# FPGA.net
KiCad netlist of a schematic drawn in Altium Designer
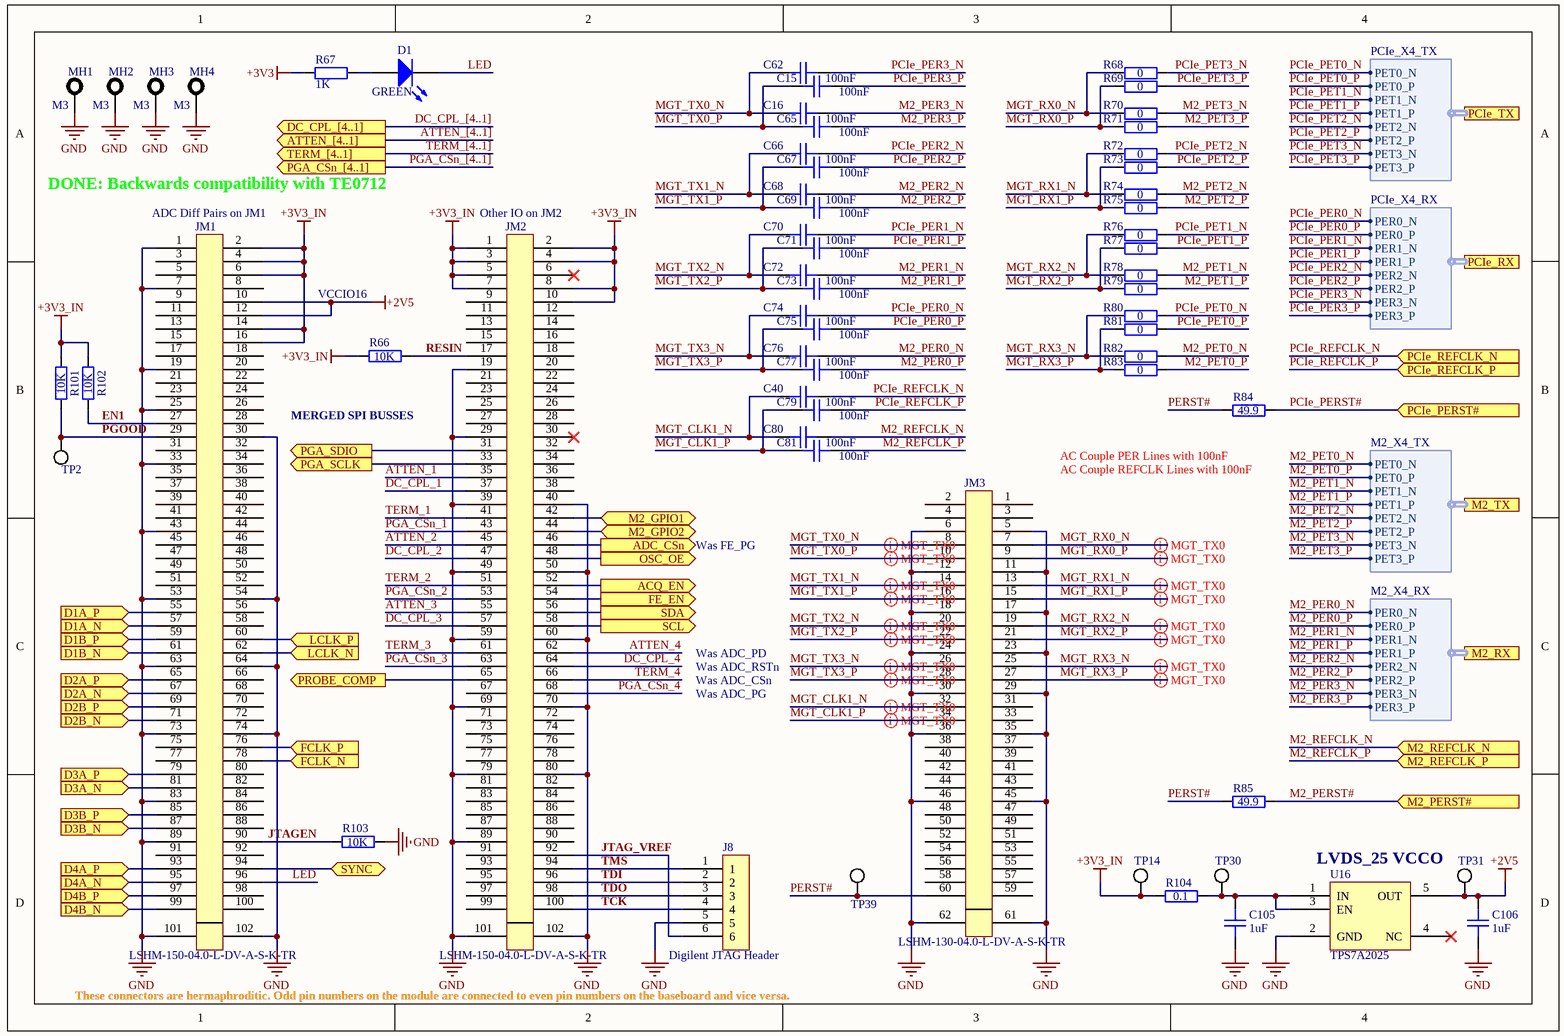
[diagram p0: FPGA.SchDoc]

(export (version "E")
  (design (tool "Eeschema 10.0.6"))
  (components
    (comp (ref "C15")
      (value "100nF")
      (footprint "GEN_C_0201")
      (libsource (lib "DSO") (part "CAP 100nF 6.3V X5R 0201"))
    )
    (comp (ref "C16")
      (value "100nF")
      (footprint "GEN_C_0201")
      (libsource (lib "DSO") (part "CAP 100nF 6.3V X5R 0201"))
    )
    (comp (ref "C40")
      (value "100nF")
      (footprint "GEN_C_0201")
      (libsource (lib "DSO") (part "CAP 100nF 6.3V X5R 0201"))
    )
    (comp (ref "C62")
      (value "100nF")
      (footprint "GEN_C_0201")
      (libsource (lib "DSO") (part "CAP 100nF 6.3V X5R 0201"))
    )
    (comp (ref "C65")
      (value "100nF")
      (footprint "GEN_C_0201")
      (libsource (lib "DSO") (part "CAP 100nF 6.3V X5R 0201"))
    )
    (comp (ref "C66")
      (value "100nF")
      (footprint "GEN_C_0201")
      (libsource (lib "DSO") (part "CAP 100nF 6.3V X5R 0201"))
    )
    (comp (ref "C67")
      (value "100nF")
      (footprint "GEN_C_0201")
      (libsource (lib "DSO") (part "CAP 100nF 6.3V X5R 0201"))
    )
    (comp (ref "C68")
      (value "100nF")
      (footprint "GEN_C_0201")
      (libsource (lib "DSO") (part "CAP 100nF 6.3V X5R 0201"))
    )
    (comp (ref "C69")
      (value "100nF")
      (footprint "GEN_C_0201")
      (libsource (lib "DSO") (part "CAP 100nF 6.3V X5R 0201"))
    )
    (comp (ref "C70")
      (value "100nF")
      (footprint "GEN_C_0201")
      (libsource (lib "DSO") (part "CAP 100nF 6.3V X5R 0201"))
    )
    (comp (ref "C71")
      (value "100nF")
      (footprint "GEN_C_0201")
      (libsource (lib "DSO") (part "CAP 100nF 6.3V X5R 0201"))
    )
    (comp (ref "C72")
      (value "100nF")
      (footprint "GEN_C_0201")
      (libsource (lib "DSO") (part "CAP 100nF 6.3V X5R 0201"))
    )
    (comp (ref "C73")
      (value "100nF")
      (footprint "GEN_C_0201")
      (libsource (lib "DSO") (part "CAP 100nF 6.3V X5R 0201"))
    )
    (comp (ref "C74")
      (value "100nF")
      (footprint "GEN_C_0201")
      (libsource (lib "DSO") (part "CAP 100nF 6.3V X5R 0201"))
    )
    (comp (ref "C75")
      (value "100nF")
      (footprint "GEN_C_0201")
      (libsource (lib "DSO") (part "CAP 100nF 6.3V X5R 0201"))
    )
    (comp (ref "C76")
      (value "100nF")
      (footprint "GEN_C_0201")
      (libsource (lib "DSO") (part "CAP 100nF 6.3V X5R 0201"))
    )
    (comp (ref "C77")
      (value "100nF")
      (footprint "GEN_C_0201")
      (libsource (lib "DSO") (part "CAP 100nF 6.3V X5R 0201"))
    )
    (comp (ref "C79")
      (value "100nF")
      (footprint "GEN_C_0201")
      (libsource (lib "DSO") (part "CAP 100nF 6.3V X5R 0201"))
    )
    (comp (ref "C80")
      (value "100nF")
      (footprint "GEN_C_0201")
      (libsource (lib "DSO") (part "CAP 100nF 6.3V X5R 0201"))
    )
    (comp (ref "C81")
      (value "100nF")
      (footprint "GEN_C_0201")
      (libsource (lib "DSO") (part "CAP 100nF 6.3V X5R 0201"))
    )
    (comp (ref "C105")
      (value "1uF")
      (footprint "GEN_C_0402")
      (libsource (lib "DSO") (part "CAP 1uF 25V X5R 0402"))
    )
    (comp (ref "C106")
      (value "1uF")
      (footprint "GEN_C_0402")
      (libsource (lib "DSO") (part "CAP 1uF 25V X5R 0402"))
    )
    (comp (ref "D1")
      (value "GREEN")
      (footprint "LED_0603_LTST-S270K")
      (libsource (lib "DSO") (part "LED GREEN 0603 LTST-S270K"))
    )
    (comp (ref "J8")
      (value "2.54mm 6 Pin TH")
      (footprint "GEN_2.54mm_6_Pin_TH_RA")
      (libsource (lib "DSO") (part "CONN 2.54mm 6 Pin TH RA"))
    )
    (comp (ref "JM1")
      (value "LSHM-150-04.0-L-DV-A-S-K-TR")
      (footprint "SAM_LSHM-150-XX.X-XX-DV-A-S")
      (libsource (lib "DSO") (part "CONN LSHM-150-04.0-L-DV-A-S-K-TR"))
    )
    (comp (ref "JM2")
      (value "LSHM-150-04.0-L-DV-A-S-K-TR")
      (footprint "SAM_LSHM-150-XX.X-XX-DV-A-S")
      (libsource (lib "DSO") (part "CONN LSHM-150-04.0-L-DV-A-S-K-TR"))
    )
    (comp (ref "JM3")
      (value "LSHM-130-04.0-L-DV-A-S-K-TR")
      (footprint "SAM_LSHM-130-XX.X-XX-DV-A-S")
      (libsource (lib "DSO") (part "CONN LSHM-130-04.0-L-DV-A-S-K-TR"))
    )
    (comp (ref "MH1") (value "M3") (footprint "MH M3") (libsource (lib "DSO") (part "MH M3")))
    (comp (ref "MH2") (value "M3") (footprint "MH M3") (libsource (lib "DSO") (part "MH M3")))
    (comp (ref "MH3") (value "M3") (footprint "MH M3") (libsource (lib "DSO") (part "MH M3")))
    (comp (ref "MH4") (value "M3") (footprint "MH M3") (libsource (lib "DSO") (part "MH M3")))
    (comp (ref "R66")
      (value "10K")
      (footprint "GEN_R_0402")
      (fields (field (name "TOLERANCE") "1%"))
      (libsource (lib "") (part "RES 10K OHM 1% 1/10W 0402_1"))
    )
    (comp (ref "R67")
      (value "1K")
      (footprint "GEN_R_0402")
      (fields (field (name "TOLERANCE") "1%"))
      (libsource (lib "DSO") (part "RES 1K OHM 1% 1/10W 0402"))
    )
    (comp (ref "R68")
      (value "0")
      (footprint "GEN_R_0201")
      (fields (field (name "TOLERANCE") "1%"))
      (libsource (lib "DSO") (part "RES 0 OHM 1% 1/20W 0201"))
    )
    (comp (ref "R69")
      (value "0")
      (footprint "GEN_R_0201")
      (fields (field (name "TOLERANCE") "1%"))
      (libsource (lib "DSO") (part "RES 0 OHM 1% 1/20W 0201"))
    )
    (comp (ref "R70")
      (value "0")
      (footprint "GEN_R_0201")
      (fields (field (name "TOLERANCE") "1%"))
      (libsource (lib "DSO") (part "RES 0 OHM 1% 1/20W 0201"))
    )
    (comp (ref "R71")
      (value "0")
      (footprint "GEN_R_0201")
      (fields (field (name "TOLERANCE") "1%"))
      (libsource (lib "DSO") (part "RES 0 OHM 1% 1/20W 0201"))
    )
    (comp (ref "R72")
      (value "0")
      (footprint "GEN_R_0201")
      (fields (field (name "TOLERANCE") "1%"))
      (libsource (lib "DSO") (part "RES 0 OHM 1% 1/20W 0201"))
    )
    (comp (ref "R73")
      (value "0")
      (footprint "GEN_R_0201")
      (fields (field (name "TOLERANCE") "1%"))
      (libsource (lib "DSO") (part "RES 0 OHM 1% 1/20W 0201"))
    )
    (comp (ref "R74")
      (value "0")
      (footprint "GEN_R_0201")
      (fields (field (name "TOLERANCE") "1%"))
      (libsource (lib "DSO") (part "RES 0 OHM 1% 1/20W 0201"))
    )
    (comp (ref "R75")
      (value "0")
      (footprint "GEN_R_0201")
      (fields (field (name "TOLERANCE") "1%"))
      (libsource (lib "DSO") (part "RES 0 OHM 1% 1/20W 0201"))
    )
    (comp (ref "R76")
      (value "0")
      (footprint "GEN_R_0201")
      (fields (field (name "TOLERANCE") "1%"))
      (libsource (lib "DSO") (part "RES 0 OHM 1% 1/20W 0201"))
    )
    (comp (ref "R77")
      (value "0")
      (footprint "GEN_R_0201")
      (fields (field (name "TOLERANCE") "1%"))
      (libsource (lib "DSO") (part "RES 0 OHM 1% 1/20W 0201"))
    )
    (comp (ref "R78")
      (value "0")
      (footprint "GEN_R_0201")
      (fields (field (name "TOLERANCE") "1%"))
      (libsource (lib "DSO") (part "RES 0 OHM 1% 1/20W 0201"))
    )
    (comp (ref "R79")
      (value "0")
      (footprint "GEN_R_0201")
      (fields (field (name "TOLERANCE") "1%"))
      (libsource (lib "DSO") (part "RES 0 OHM 1% 1/20W 0201"))
    )
    (comp (ref "R80")
      (value "0")
      (footprint "GEN_R_0201")
      (fields (field (name "TOLERANCE") "1%"))
      (libsource (lib "DSO") (part "RES 0 OHM 1% 1/20W 0201"))
    )
    (comp (ref "R81")
      (value "0")
      (footprint "GEN_R_0201")
      (fields (field (name "TOLERANCE") "1%"))
      (libsource (lib "DSO") (part "RES 0 OHM 1% 1/20W 0201"))
    )
    (comp (ref "R82")
      (value "0")
      (footprint "GEN_R_0201")
      (fields (field (name "TOLERANCE") "1%"))
      (libsource (lib "DSO") (part "RES 0 OHM 1% 1/20W 0201"))
    )
    (comp (ref "R83")
      (value "0")
      (footprint "GEN_R_0201")
      (fields (field (name "TOLERANCE") "1%"))
      (libsource (lib "DSO") (part "RES 0 OHM 1% 1/20W 0201"))
    )
    (comp (ref "R84")
      (value "49.9")
      (footprint "GEN_R_0402")
      (fields (field (name "TOLERANCE") "1%"))
      (libsource (lib "DSO") (part "RES 49.9 OHM 1% 1/10W 0402"))
    )
    (comp (ref "R85")
      (value "49.9")
      (footprint "GEN_R_0402")
      (fields (field (name "TOLERANCE") "1%"))
      (libsource (lib "DSO") (part "RES 49.9 OHM 1% 1/10W 0402"))
    )
    (comp (ref "R101")
      (value "10K")
      (footprint "GEN_R_0402")
      (fields (field (name "TOLERANCE") "1%"))
      (libsource (lib "DSO") (part "RES 10K OHM 1% 1/10W 0402"))
    )
    (comp (ref "R102")
      (value "10K")
      (footprint "GEN_R_0402")
      (fields (field (name "TOLERANCE") "1%"))
      (libsource (lib "DSO") (part "RES 10K OHM 1% 1/10W 0402"))
    )
    (comp (ref "R103")
      (value "10K")
      (footprint "GEN_R_0402")
      (fields (field (name "TOLERANCE") "1%"))
      (libsource (lib "") (part "RES 10K OHM 1% 1/10W 0402_1"))
    )
    (comp (ref "R104")
      (value "0.1")
      (footprint "GEN_R_0402")
      (fields (field (name "TOLERANCE") "1%"))
      (libsource (lib "DSO") (part "RES 0.1 OHM 1% 1/6W 0402"))
    )
    (comp (ref "TP2") (value "PCB") (footprint "GEN_TP_PCB") (libsource (lib "DSO") (part "TP PCB 1mm")))
    (comp (ref "TP14") (value "PCB") (footprint "GEN_TP_PCB") (libsource (lib "DSO") (part "TP PCB 1mm")))
    (comp (ref "TP30") (value "PCB") (footprint "GEN_TP_PCB") (libsource (lib "DSO") (part "TP PCB 1mm")))
    (comp (ref "TP31") (value "PCB") (footprint "GEN_TP_PCB") (libsource (lib "DSO") (part "TP PCB 1mm")))
    (comp (ref "TP39") (value "PCB") (footprint "GEN_TP_PCB") (libsource (lib "DSO") (part "TP PCB 1mm")))
    (comp (ref "U16")
      (value "TPS7A2025")
      (footprint "GEN_SOT23_5_950_2900X1600X1450")
      (libsource (lib "DSO") (part "IC LDO TPS7A2025"))
    )
  )
  (nets
    (net (code "5") (name "+2V5") (class "Default")
      (node (ref "C106") (pin "2") (pinfunction "2_2") (pintype "passive"))
      (node (ref "JM1") (pin "10") (pinfunction "10_10") (pintype "passive"))
      (node (ref "JM1") (pin "12") (pinfunction "12_12") (pintype "passive"))
      (node (ref "TP31") (pin "1") (pinfunction "1_1") (pintype "passive"))
      (node (ref "U16") (pin "5") (pinfunction "OUT_5") (pintype "power_in"))
    )
    (net (code "6") (name "+3V3") (class "Default")
      (node (ref "R67") (pin "2") (pinfunction "2_2") (pintype "passive"))
    )
    (net (code "7") (name "+3V3_IN") (class "Default")
      (node (ref "JM1") (pin "14") (pinfunction "14_14") (pintype "passive"))
      (node (ref "JM1") (pin "16") (pinfunction "16_16") (pintype "passive"))
      (node (ref "JM1") (pin "2") (pinfunction "2_2") (pintype "passive"))
      (node (ref "JM1") (pin "4") (pinfunction "4_4") (pintype "passive"))
      (node (ref "JM1") (pin "6") (pinfunction "6_6") (pintype "passive"))
      (node (ref "JM2") (pin "1") (pinfunction "1_1") (pintype "passive"))
      (node (ref "JM2") (pin "10") (pinfunction "10_10") (pintype "passive"))
      (node (ref "JM2") (pin "2") (pinfunction "2_2") (pintype "passive"))
      (node (ref "JM2") (pin "3") (pinfunction "3_3") (pintype "passive"))
      (node (ref "JM2") (pin "4") (pinfunction "4_4") (pintype "passive"))
      (node (ref "JM2") (pin "5") (pinfunction "5_5") (pintype "passive"))
      (node (ref "JM2") (pin "7") (pinfunction "7_7") (pintype "passive"))
      (node (ref "JM2") (pin "8") (pinfunction "8_8") (pintype "passive"))
      (node (ref "R101") (pin "2") (pinfunction "2_2") (pintype "passive"))
      (node (ref "R102") (pin "2") (pinfunction "2_2") (pintype "passive"))
      (node (ref "R104") (pin "1") (pinfunction "1_1") (pintype "passive"))
      (node (ref "R66") (pin "2") (pinfunction "2_2") (pintype "passive"))
      (node (ref "TP14") (pin "1") (pinfunction "1_1") (pintype "passive"))
    )
    (net (code "8") (name "/ACQ_EN") (class "Default")
      (node (ref "JM2") (pin "52") (pinfunction "52_52") (pintype "passive"))
    )
    (net (code "9") (name "/ADC_CSn") (class "Default")
      (node (ref "JM2") (pin "46") (pinfunction "46_46") (pintype "passive"))
    )
    (net (code "10") (name "/ATTEN_1") (class "Default")
      (node (ref "JM2") (pin "35") (pinfunction "35_35") (pintype "passive"))
    )
    (net (code "11") (name "/ATTEN_2") (class "Default")
      (node (ref "JM2") (pin "45") (pinfunction "45_45") (pintype "passive"))
    )
    (net (code "12") (name "/ATTEN_3") (class "Default")
      (node (ref "JM2") (pin "55") (pinfunction "55_55") (pintype "passive"))
    )
    (net (code "13") (name "/ATTEN_4") (class "Default")
      (node (ref "JM2") (pin "62") (pinfunction "62_62") (pintype "passive"))
    )
    (net (code "15") (name "/D1A_N") (class "Default")
      (node (ref "JM1") (pin "57") (pinfunction "57_57") (pintype "passive"))
    )
    (net (code "16") (name "/D1A_P") (class "Default")
      (node (ref "JM1") (pin "55") (pinfunction "55_55") (pintype "passive"))
    )
    (net (code "17") (name "/D1B_N") (class "Default")
      (node (ref "JM1") (pin "61") (pinfunction "61_61") (pintype "passive"))
    )
    (net (code "18") (name "/D1B_P") (class "Default")
      (node (ref "JM1") (pin "59") (pinfunction "59_59") (pintype "passive"))
    )
    (net (code "19") (name "/D2A_N") (class "Default")
      (node (ref "JM1") (pin "67") (pinfunction "67_67") (pintype "passive"))
    )
    (net (code "20") (name "/D2A_P") (class "Default")
      (node (ref "JM1") (pin "65") (pinfunction "65_65") (pintype "passive"))
    )
    (net (code "21") (name "/D2B_N") (class "Default")
      (node (ref "JM1") (pin "71") (pinfunction "71_71") (pintype "passive"))
    )
    (net (code "22") (name "/D2B_P") (class "Default")
      (node (ref "JM1") (pin "69") (pinfunction "69_69") (pintype "passive"))
    )
    (net (code "23") (name "/D3A_N") (class "Default")
      (node (ref "JM1") (pin "81") (pinfunction "81_81") (pintype "passive"))
    )
    (net (code "24") (name "/D3A_P") (class "Default")
      (node (ref "JM1") (pin "79") (pinfunction "79_79") (pintype "passive"))
    )
    (net (code "25") (name "/D3B_N") (class "Default")
      (node (ref "JM1") (pin "87") (pinfunction "87_87") (pintype "passive"))
    )
    (net (code "26") (name "/D3B_P") (class "Default")
      (node (ref "JM1") (pin "85") (pinfunction "85_85") (pintype "passive"))
    )
    (net (code "27") (name "/D4A_N") (class "Default")
      (node (ref "JM1") (pin "95") (pinfunction "95_95") (pintype "passive"))
    )
    (net (code "28") (name "/D4A_P") (class "Default")
      (node (ref "JM1") (pin "93") (pinfunction "93_93") (pintype "passive"))
    )
    (net (code "29") (name "/D4B_N") (class "Default")
      (node (ref "JM1") (pin "99") (pinfunction "99_99") (pintype "passive"))
    )
    (net (code "30") (name "/D4B_P") (class "Default")
      (node (ref "JM1") (pin "97") (pinfunction "97_97") (pintype "passive"))
    )
    (net (code "31") (name "/DC_CPL_1") (class "Default")
      (node (ref "JM2") (pin "37") (pinfunction "37_37") (pintype "passive"))
    )
    (net (code "32") (name "/DC_CPL_2") (class "Default")
      (node (ref "JM2") (pin "47") (pinfunction "47_47") (pintype "passive"))
    )
    (net (code "33") (name "/DC_CPL_3") (class "Default")
      (node (ref "JM2") (pin "57") (pinfunction "57_57") (pintype "passive"))
    )
    (net (code "34") (name "/DC_CPL_4") (class "Default")
      (node (ref "JM2") (pin "64") (pinfunction "64_64") (pintype "passive"))
    )
    (net (code "36") (name "/EN1") (class "Default")
      (node (ref "JM1") (pin "27") (pinfunction "27_27") (pintype "passive"))
      (node (ref "R102") (pin "1") (pinfunction "1_1") (pintype "passive"))
    )
    (net (code "37") (name "/FCLK_N") (class "Default")
      (node (ref "JM1") (pin "78") (pinfunction "78_78") (pintype "passive"))
    )
    (net (code "38") (name "/FCLK_P") (class "Default")
      (node (ref "JM1") (pin "76") (pinfunction "76_76") (pintype "passive"))
    )
    (net (code "39") (name "/FE_EN") (class "Default")
      (node (ref "JM2") (pin "54") (pinfunction "54_54") (pintype "passive"))
    )
    (net (code "40") (name "/JTAGEN") (class "Default")
      (node (ref "JM1") (pin "90") (pinfunction "90_90") (pintype "passive"))
      (node (ref "R103") (pin "2") (pinfunction "2_2") (pintype "passive"))
    )
    (net (code "41") (name "/JTAG_VREF") (class "Default")
      (node (ref "J8") (pin "6") (pinfunction "6_6") (pintype "passive"))
      (node (ref "JM2") (pin "92") (pinfunction "92_92") (pintype "passive"))
    )
    (net (code "42") (name "/LCLK_N") (class "Default")
      (node (ref "JM1") (pin "62") (pinfunction "62_62") (pintype "passive"))
    )
    (net (code "43") (name "/LCLK_P") (class "Default")
      (node (ref "JM1") (pin "60") (pinfunction "60_60") (pintype "passive"))
    )
    (net (code "44") (name "/LED") (class "Default")
      (node (ref "D1") (pin "1") (pinfunction "K_1") (pintype "passive"))
      (node (ref "JM1") (pin "96") (pinfunction "96_96") (pintype "passive"))
    )
    (net (code "45") (name "/M2_GPIO1") (class "Default")
      (node (ref "JM2") (pin "42") (pinfunction "42_42") (pintype "passive"))
    )
    (net (code "46") (name "/M2_GPIO2") (class "Default")
      (node (ref "JM2") (pin "44") (pinfunction "44_44") (pintype "passive"))
    )
    (net (code "47") (name "/M2_PER0_N") (class "Default")
      (node (ref "C76") (pin "1") (pinfunction "1_1") (pintype "passive"))
    )
    (net (code "48") (name "/M2_PER0_P") (class "Default")
      (node (ref "C77") (pin "1") (pinfunction "1_1") (pintype "passive"))
    )
    (net (code "49") (name "/M2_PER1_N") (class "Default")
      (node (ref "C72") (pin "1") (pinfunction "1_1") (pintype "passive"))
    )
    (net (code "50") (name "/M2_PER1_P") (class "Default")
      (node (ref "C73") (pin "1") (pinfunction "1_1") (pintype "passive"))
    )
    (net (code "51") (name "/M2_PER2_N") (class "Default")
      (node (ref "C68") (pin "1") (pinfunction "1_1") (pintype "passive"))
    )
    (net (code "52") (name "/M2_PER2_P") (class "Default")
      (node (ref "C69") (pin "1") (pinfunction "1_1") (pintype "passive"))
    )
    (net (code "53") (name "/M2_PER3_N") (class "Default")
      (node (ref "C16") (pin "1") (pinfunction "1_1") (pintype "passive"))
    )
    (net (code "54") (name "/M2_PER3_P") (class "Default")
      (node (ref "C65") (pin "1") (pinfunction "1_1") (pintype "passive"))
    )
    (net (code "55") (name "/M2_PERST#") (class "Default")
      (node (ref "R85") (pin "2") (pinfunction "2_2") (pintype "passive"))
    )
    (net (code "56") (name "/M2_PET0_N") (class "Default")
      (node (ref "R82") (pin "2") (pinfunction "2_2") (pintype "passive"))
    )
    (net (code "57") (name "/M2_PET0_P") (class "Default")
      (node (ref "R83") (pin "2") (pinfunction "2_2") (pintype "passive"))
    )
    (net (code "58") (name "/M2_PET1_N") (class "Default")
      (node (ref "R78") (pin "2") (pinfunction "2_2") (pintype "passive"))
    )
    (net (code "59") (name "/M2_PET1_P") (class "Default")
      (node (ref "R79") (pin "2") (pinfunction "2_2") (pintype "passive"))
    )
    (net (code "60") (name "/M2_PET2_N") (class "Default")
      (node (ref "R74") (pin "2") (pinfunction "2_2") (pintype "passive"))
    )
    (net (code "61") (name "/M2_PET2_P") (class "Default")
      (node (ref "R75") (pin "2") (pinfunction "2_2") (pintype "passive"))
    )
    (net (code "62") (name "/M2_PET3_N") (class "Default")
      (node (ref "R70") (pin "2") (pinfunction "2_2") (pintype "passive"))
    )
    (net (code "63") (name "/M2_PET3_P") (class "Default")
      (node (ref "R71") (pin "2") (pinfunction "2_2") (pintype "passive"))
    )
    (net (code "64") (name "/M2_REFCLK_N") (class "Default")
      (node (ref "C80") (pin "1") (pinfunction "1_1") (pintype "passive"))
    )
    (net (code "65") (name "/M2_REFCLK_P") (class "Default")
      (node (ref "C81") (pin "1") (pinfunction "1_1") (pintype "passive"))
    )
    (net (code "66") (name "/MGT_CLK1_N") (class "Default")
      (node (ref "C40") (pin "2") (pinfunction "2_2") (pintype "passive"))
      (node (ref "C80") (pin "2") (pinfunction "2_2") (pintype "passive"))
      (node (ref "JM3") (pin "32") (pinfunction "32_32") (pintype "passive"))
    )
    (net (code "67") (name "/MGT_CLK1_P") (class "Default")
      (node (ref "C79") (pin "2") (pinfunction "2_2") (pintype "passive"))
      (node (ref "C81") (pin "2") (pinfunction "2_2") (pintype "passive"))
      (node (ref "JM3") (pin "34") (pinfunction "34_34") (pintype "passive"))
    )
    (net (code "68") (name "/MGT_RX0_N") (class "Default")
      (node (ref "JM3") (pin "7") (pinfunction "7_7") (pintype "passive"))
      (node (ref "R68") (pin "1") (pinfunction "1_1") (pintype "passive"))
      (node (ref "R70") (pin "1") (pinfunction "1_1") (pintype "passive"))
    )
    (net (code "69") (name "/MGT_RX0_P") (class "Default")
      (node (ref "JM3") (pin "9") (pinfunction "9_9") (pintype "passive"))
      (node (ref "R69") (pin "1") (pinfunction "1_1") (pintype "passive"))
      (node (ref "R71") (pin "1") (pinfunction "1_1") (pintype "passive"))
    )
    (net (code "70") (name "/MGT_RX1_N") (class "Default")
      (node (ref "JM3") (pin "13") (pinfunction "13_13") (pintype "passive"))
      (node (ref "R72") (pin "1") (pinfunction "1_1") (pintype "passive"))
      (node (ref "R74") (pin "1") (pinfunction "1_1") (pintype "passive"))
    )
    (net (code "71") (name "/MGT_RX1_P") (class "Default")
      (node (ref "JM3") (pin "15") (pinfunction "15_15") (pintype "passive"))
      (node (ref "R73") (pin "1") (pinfunction "1_1") (pintype "passive"))
      (node (ref "R75") (pin "1") (pinfunction "1_1") (pintype "passive"))
    )
    (net (code "72") (name "/MGT_RX2_N") (class "Default")
      (node (ref "JM3") (pin "19") (pinfunction "19_19") (pintype "passive"))
      (node (ref "R76") (pin "1") (pinfunction "1_1") (pintype "passive"))
      (node (ref "R78") (pin "1") (pinfunction "1_1") (pintype "passive"))
    )
    (net (code "73") (name "/MGT_RX2_P") (class "Default")
      (node (ref "JM3") (pin "21") (pinfunction "21_21") (pintype "passive"))
      (node (ref "R77") (pin "1") (pinfunction "1_1") (pintype "passive"))
      (node (ref "R79") (pin "1") (pinfunction "1_1") (pintype "passive"))
    )
    (net (code "74") (name "/MGT_RX3_N") (class "Default")
      (node (ref "JM3") (pin "25") (pinfunction "25_25") (pintype "passive"))
      (node (ref "R80") (pin "1") (pinfunction "1_1") (pintype "passive"))
      (node (ref "R82") (pin "1") (pinfunction "1_1") (pintype "passive"))
    )
    (net (code "75") (name "/MGT_RX3_P") (class "Default")
      (node (ref "JM3") (pin "27") (pinfunction "27_27") (pintype "passive"))
      (node (ref "R81") (pin "1") (pinfunction "1_1") (pintype "passive"))
      (node (ref "R83") (pin "1") (pinfunction "1_1") (pintype "passive"))
    )
    (net (code "76") (name "/MGT_TX0_N") (class "Default")
      (node (ref "C16") (pin "2") (pinfunction "2_2") (pintype "passive"))
      (node (ref "C62") (pin "2") (pinfunction "2_2") (pintype "passive"))
      (node (ref "JM3") (pin "8") (pinfunction "8_8") (pintype "passive"))
    )
    (net (code "77") (name "/MGT_TX0_P") (class "Default")
      (node (ref "C15") (pin "2") (pinfunction "2_2") (pintype "passive"))
      (node (ref "C65") (pin "2") (pinfunction "2_2") (pintype "passive"))
      (node (ref "JM3") (pin "10") (pinfunction "10_10") (pintype "passive"))
    )
    (net (code "78") (name "/MGT_TX1_N") (class "Default")
      (node (ref "C66") (pin "2") (pinfunction "2_2") (pintype "passive"))
      (node (ref "C68") (pin "2") (pinfunction "2_2") (pintype "passive"))
      (node (ref "JM3") (pin "14") (pinfunction "14_14") (pintype "passive"))
    )
    (net (code "79") (name "/MGT_TX1_P") (class "Default")
      (node (ref "C67") (pin "2") (pinfunction "2_2") (pintype "passive"))
      (node (ref "C69") (pin "2") (pinfunction "2_2") (pintype "passive"))
      (node (ref "JM3") (pin "16") (pinfunction "16_16") (pintype "passive"))
    )
    (net (code "80") (name "/MGT_TX2_N") (class "Default")
      (node (ref "C70") (pin "2") (pinfunction "2_2") (pintype "passive"))
      (node (ref "C72") (pin "2") (pinfunction "2_2") (pintype "passive"))
      (node (ref "JM3") (pin "20") (pinfunction "20_20") (pintype "passive"))
    )
    (net (code "81") (name "/MGT_TX2_P") (class "Default")
      (node (ref "C71") (pin "2") (pinfunction "2_2") (pintype "passive"))
      (node (ref "C73") (pin "2") (pinfunction "2_2") (pintype "passive"))
      (node (ref "JM3") (pin "22") (pinfunction "22_22") (pintype "passive"))
    )
    (net (code "82") (name "/MGT_TX3_N") (class "Default")
      (node (ref "C74") (pin "2") (pinfunction "2_2") (pintype "passive"))
      (node (ref "C76") (pin "2") (pinfunction "2_2") (pintype "passive"))
      (node (ref "JM3") (pin "26") (pinfunction "26_26") (pintype "passive"))
    )
    (net (code "83") (name "/MGT_TX3_P") (class "Default")
      (node (ref "C75") (pin "2") (pinfunction "2_2") (pintype "passive"))
      (node (ref "C77") (pin "2") (pinfunction "2_2") (pintype "passive"))
      (node (ref "JM3") (pin "28") (pinfunction "28_28") (pintype "passive"))
    )
    (net (code "84") (name "/OSC_OE") (class "Default")
      (node (ref "JM2") (pin "48") (pinfunction "48_48") (pintype "passive"))
    )
    (net (code "85") (name "/PCIe_PER0_N") (class "Default")
      (node (ref "C74") (pin "1") (pinfunction "1_1") (pintype "passive"))
    )
    (net (code "86") (name "/PCIe_PER0_P") (class "Default")
      (node (ref "C75") (pin "1") (pinfunction "1_1") (pintype "passive"))
    )
    (net (code "87") (name "/PCIe_PER1_N") (class "Default")
      (node (ref "C70") (pin "1") (pinfunction "1_1") (pintype "passive"))
    )
    (net (code "88") (name "/PCIe_PER1_P") (class "Default")
      (node (ref "C71") (pin "1") (pinfunction "1_1") (pintype "passive"))
    )
    (net (code "89") (name "/PCIe_PER2_N") (class "Default")
      (node (ref "C66") (pin "1") (pinfunction "1_1") (pintype "passive"))
    )
    (net (code "90") (name "/PCIe_PER2_P") (class "Default")
      (node (ref "C67") (pin "1") (pinfunction "1_1") (pintype "passive"))
    )
    (net (code "91") (name "/PCIe_PER3_N") (class "Default")
      (node (ref "C62") (pin "1") (pinfunction "1_1") (pintype "passive"))
    )
    (net (code "92") (name "/PCIe_PER3_P") (class "Default")
      (node (ref "C15") (pin "1") (pinfunction "1_1") (pintype "passive"))
    )
    (net (code "93") (name "/PCIe_PERST#") (class "Default")
      (node (ref "R84") (pin "2") (pinfunction "2_2") (pintype "passive"))
    )
    (net (code "94") (name "/PCIe_PET0_N") (class "Default")
      (node (ref "R80") (pin "2") (pinfunction "2_2") (pintype "passive"))
    )
    (net (code "95") (name "/PCIe_PET0_P") (class "Default")
      (node (ref "R81") (pin "2") (pinfunction "2_2") (pintype "passive"))
    )
    (net (code "96") (name "/PCIe_PET1_N") (class "Default")
      (node (ref "R76") (pin "2") (pinfunction "2_2") (pintype "passive"))
    )
    (net (code "97") (name "/PCIe_PET1_P") (class "Default")
      (node (ref "R77") (pin "2") (pinfunction "2_2") (pintype "passive"))
    )
    (net (code "98") (name "/PCIe_PET2_N") (class "Default")
      (node (ref "R72") (pin "2") (pinfunction "2_2") (pintype "passive"))
    )
    (net (code "99") (name "/PCIe_PET2_P") (class "Default")
      (node (ref "R73") (pin "2") (pinfunction "2_2") (pintype "passive"))
    )
    (net (code "100") (name "/PCIe_PET3_N") (class "Default")
      (node (ref "R68") (pin "2") (pinfunction "2_2") (pintype "passive"))
    )
    (net (code "101") (name "/PCIe_PET3_P") (class "Default")
      (node (ref "R69") (pin "2") (pinfunction "2_2") (pintype "passive"))
    )
    (net (code "102") (name "/PCIe_REFCLK_N") (class "Default")
      (node (ref "C40") (pin "1") (pinfunction "1_1") (pintype "passive"))
    )
    (net (code "103") (name "/PCIe_REFCLK_P") (class "Default")
      (node (ref "C79") (pin "1") (pinfunction "1_1") (pintype "passive"))
    )
    (net (code "104") (name "/PERST#") (class "Default")
      (node (ref "JM3") (pin "60") (pinfunction "60_60") (pintype "passive"))
      (node (ref "R84") (pin "1") (pinfunction "1_1") (pintype "passive"))
      (node (ref "R85") (pin "1") (pinfunction "1_1") (pintype "passive"))
      (node (ref "TP39") (pin "1") (pinfunction "1_1") (pintype "passive"))
    )
    (net (code "105") (name "/PGA_CSn_1") (class "Default")
      (node (ref "JM2") (pin "43") (pinfunction "43_43") (pintype "passive"))
    )
    (net (code "106") (name "/PGA_CSn_2") (class "Default")
      (node (ref "JM2") (pin "53") (pinfunction "53_53") (pintype "passive"))
    )
    (net (code "107") (name "/PGA_CSn_3") (class "Default")
      (node (ref "JM2") (pin "63") (pinfunction "63_63") (pintype "passive"))
    )
    (net (code "108") (name "/PGA_CSn_4") (class "Default")
      (node (ref "JM2") (pin "68") (pinfunction "68_68") (pintype "passive"))
    )
    (net (code "110") (name "/PGA_SCLK") (class "Default")
      (node (ref "JM2") (pin "33") (pinfunction "33_33") (pintype "passive"))
    )
    (net (code "111") (name "/PGA_SDIO") (class "Default")
      (node (ref "JM2") (pin "31") (pinfunction "31_31") (pintype "passive"))
    )
    (net (code "112") (name "/PGOOD") (class "Default")
      (node (ref "JM1") (pin "29") (pinfunction "29_29") (pintype "passive"))
      (node (ref "R101") (pin "1") (pinfunction "1_1") (pintype "passive"))
      (node (ref "TP2") (pin "1") (pinfunction "1_1") (pintype "passive"))
    )
    (net (code "113") (name "/PROBE_COMP") (class "Default")
      (node (ref "JM2") (pin "65") (pinfunction "65_65") (pintype "passive"))
    )
    (net (code "114") (name "/RESIN") (class "Default")
      (node (ref "JM2") (pin "17") (pinfunction "17_17") (pintype "passive"))
      (node (ref "R66") (pin "1") (pinfunction "1_1") (pintype "passive"))
    )
    (net (code "115") (name "/SCL") (class "Default")
      (node (ref "JM2") (pin "58") (pinfunction "58_58") (pintype "passive"))
    )
    (net (code "116") (name "/SDA") (class "Default")
      (node (ref "JM2") (pin "56") (pinfunction "56_56") (pintype "passive"))
    )
    (net (code "117") (name "/SYNC") (class "Default")
      (node (ref "JM1") (pin "94") (pinfunction "94_94") (pintype "passive"))
    )
    (net (code "118") (name "/TCK") (class "Default")
      (node (ref "J8") (pin "4") (pinfunction "4_4") (pintype "passive"))
      (node (ref "JM2") (pin "100") (pinfunction "100_100") (pintype "passive"))
    )
    (net (code "119") (name "/TDI") (class "Default")
      (node (ref "J8") (pin "2") (pinfunction "2_2") (pintype "passive"))
      (node (ref "JM2") (pin "96") (pinfunction "96_96") (pintype "passive"))
    )
    (net (code "120") (name "/TDO") (class "Default")
      (node (ref "J8") (pin "3") (pinfunction "3_3") (pintype "passive"))
      (node (ref "JM2") (pin "98") (pinfunction "98_98") (pintype "passive"))
    )
    (net (code "121") (name "/TERM_1") (class "Default")
      (node (ref "JM2") (pin "41") (pinfunction "41_41") (pintype "passive"))
    )
    (net (code "122") (name "/TERM_2") (class "Default")
      (node (ref "JM2") (pin "51") (pinfunction "51_51") (pintype "passive"))
    )
    (net (code "123") (name "/TERM_3") (class "Default")
      (node (ref "JM2") (pin "61") (pinfunction "61_61") (pintype "passive"))
    )
    (net (code "124") (name "/TERM_4") (class "Default")
      (node (ref "JM2") (pin "66") (pinfunction "66_66") (pintype "passive"))
    )
    (net (code "126") (name "/TMS") (class "Default")
      (node (ref "J8") (pin "1") (pinfunction "1_1") (pintype "passive"))
      (node (ref "JM2") (pin "94") (pinfunction "94_94") (pintype "passive"))
    )
    (net (code "131") (name "GND") (class "Default")
      (node (ref "C105") (pin "1") (pinfunction "1_1") (pintype "passive"))
      (node (ref "C106") (pin "1") (pinfunction "1_1") (pintype "passive"))
      (node (ref "J8") (pin "5") (pinfunction "5_5") (pintype "passive"))
      (node (ref "JM1") (pin "1") (pinfunction "1_1") (pintype "passive"))
      (node (ref "JM1") (pin "101") (pinfunction "101_101") (pintype "passive"))
      (node (ref "JM1") (pin "102") (pinfunction "102_102") (pintype "passive"))
      (node (ref "JM1") (pin "19") (pinfunction "19_19") (pintype "passive"))
      (node (ref "JM1") (pin "25") (pinfunction "25_25") (pintype "passive"))
      (node (ref "JM1") (pin "30") (pinfunction "30_30") (pintype "passive"))
      (node (ref "JM1") (pin "33") (pinfunction "33_33") (pintype "passive"))
      (node (ref "JM1") (pin "43") (pinfunction "43_43") (pintype "passive"))
      (node (ref "JM1") (pin "53") (pinfunction "53_53") (pintype "passive"))
      (node (ref "JM1") (pin "54") (pinfunction "54_54") (pintype "passive"))
      (node (ref "JM1") (pin "63") (pinfunction "63_63") (pintype "passive"))
      (node (ref "JM1") (pin "64") (pinfunction "64_64") (pintype "passive"))
      (node (ref "JM1") (pin "7") (pinfunction "7_7") (pintype "passive"))
      (node (ref "JM1") (pin "73") (pinfunction "73_73") (pintype "passive"))
      (node (ref "JM1") (pin "74") (pinfunction "74_74") (pintype "passive"))
      (node (ref "JM1") (pin "83") (pinfunction "83_83") (pintype "passive"))
      (node (ref "JM1") (pin "89") (pinfunction "89_89") (pintype "passive"))
      (node (ref "JM2") (pin "101") (pinfunction "101_101") (pintype "passive"))
      (node (ref "JM2") (pin "102") (pinfunction "102_102") (pintype "passive"))
      (node (ref "JM2") (pin "19") (pinfunction "19_19") (pintype "passive"))
      (node (ref "JM2") (pin "29") (pinfunction "29_29") (pintype "passive"))
      (node (ref "JM2") (pin "39") (pinfunction "39_39") (pintype "passive"))
      (node (ref "JM2") (pin "40") (pinfunction "40_40") (pintype "passive"))
      (node (ref "JM2") (pin "49") (pinfunction "49_49") (pintype "passive"))
      (node (ref "JM2") (pin "50") (pinfunction "50_50") (pintype "passive"))
      (node (ref "JM2") (pin "59") (pinfunction "59_59") (pintype "passive"))
      (node (ref "JM2") (pin "60") (pinfunction "60_60") (pintype "passive"))
      (node (ref "JM2") (pin "69") (pinfunction "69_69") (pintype "passive"))
      (node (ref "JM2") (pin "70") (pinfunction "70_70") (pintype "passive"))
      (node (ref "JM2") (pin "79") (pinfunction "79_79") (pintype "passive"))
      (node (ref "JM2") (pin "80") (pinfunction "80_80") (pintype "passive"))
      (node (ref "JM2") (pin "89") (pinfunction "89_89") (pintype "passive"))
      (node (ref "JM3") (pin "11") (pinfunction "11_11") (pintype "passive"))
      (node (ref "JM3") (pin "12") (pinfunction "12_12") (pintype "passive"))
      (node (ref "JM3") (pin "17") (pinfunction "17_17") (pintype "passive"))
      (node (ref "JM3") (pin "18") (pinfunction "18_18") (pintype "passive"))
      (node (ref "JM3") (pin "23") (pinfunction "23_23") (pintype "passive"))
      (node (ref "JM3") (pin "24") (pinfunction "24_24") (pintype "passive"))
      (node (ref "JM3") (pin "29") (pinfunction "29_29") (pintype "passive"))
      (node (ref "JM3") (pin "30") (pinfunction "30_30") (pintype "passive"))
      (node (ref "JM3") (pin "35") (pinfunction "35_35") (pintype "passive"))
      (node (ref "JM3") (pin "36") (pinfunction "36_36") (pintype "passive"))
      (node (ref "JM3") (pin "45") (pinfunction "45_45") (pintype "passive"))
      (node (ref "JM3") (pin "46") (pinfunction "46_46") (pintype "passive"))
      (node (ref "JM3") (pin "5") (pinfunction "5_5") (pintype "passive"))
      (node (ref "JM3") (pin "6") (pinfunction "6_6") (pintype "passive"))
      (node (ref "JM3") (pin "61") (pinfunction "61_61") (pintype "passive"))
      (node (ref "JM3") (pin "62") (pinfunction "62_62") (pintype "passive"))
      (node (ref "MH1") (pin "1") (pinfunction "1_1") (pintype "passive"))
      (node (ref "MH2") (pin "1") (pinfunction "1_1") (pintype "passive"))
      (node (ref "MH3") (pin "1") (pinfunction "1_1") (pintype "passive"))
      (node (ref "MH4") (pin "1") (pinfunction "1_1") (pintype "passive"))
      (node (ref "R103") (pin "1") (pinfunction "1_1") (pintype "passive"))
      (node (ref "U16") (pin "2") (pinfunction "GND_2") (pintype "power_in"))
    )
    (net (code "132") (name "Net-(D1-A)") (class "Default")
      (node (ref "D1") (pin "2") (pinfunction "A_2") (pintype "passive"))
      (node (ref "R67") (pin "1") (pinfunction "1_1") (pintype "passive"))
    )
    (net (code "133") (name "Net-(U16-EN)") (class "Default")
      (node (ref "C105") (pin "2") (pinfunction "2_2") (pintype "passive"))
      (node (ref "R104") (pin "2") (pinfunction "2_2") (pintype "passive"))
      (node (ref "TP30") (pin "1") (pinfunction "1_1") (pintype "passive"))
      (node (ref "U16") (pin "1") (pinfunction "IN_1") (pintype "power_in"))
      (node (ref "U16") (pin "3") (pinfunction "EN_3") (pintype "passive"))
    )
    (net (code "134") (name "unconnected-(JM1-Pad3)") (class "Default")
      (node (ref "JM1") (pin "3") (pinfunction "3_3") (pintype "passive"))
    )
    (net (code "135") (name "unconnected-(JM1-Pad5)") (class "Default")
      (node (ref "JM1") (pin "5") (pinfunction "5_5") (pintype "passive"))
    )
    (net (code "136") (name "unconnected-(JM1-Pad8)") (class "Default")
      (node (ref "JM1") (pin "8") (pinfunction "8_8") (pintype "passive"))
    )
    (net (code "137") (name "unconnected-(JM1-Pad9)") (class "Default")
      (node (ref "JM1") (pin "9") (pinfunction "9_9") (pintype "passive"))
    )
    (net (code "138") (name "unconnected-(JM1-Pad11)") (class "Default")
      (node (ref "JM1") (pin "11") (pinfunction "11_11") (pintype "passive"))
    )
    (net (code "139") (name "unconnected-(JM1-Pad13)") (class "Default")
      (node (ref "JM1") (pin "13") (pinfunction "13_13") (pintype "passive"))
    )
    (net (code "140") (name "unconnected-(JM1-Pad15)") (class "Default")
      (node (ref "JM1") (pin "15") (pinfunction "15_15") (pintype "passive"))
    )
    (net (code "141") (name "unconnected-(JM1-Pad17)") (class "Default")
      (node (ref "JM1") (pin "17") (pinfunction "17_17") (pintype "passive"))
    )
    (net (code "142") (name "unconnected-(JM1-Pad18)") (class "Default")
      (node (ref "JM1") (pin "18") (pinfunction "18_18") (pintype "passive"))
    )
    (net (code "143") (name "unconnected-(JM1-Pad20)") (class "Default")
      (node (ref "JM1") (pin "20") (pinfunction "20_20") (pintype "passive"))
    )
    (net (code "144") (name "unconnected-(JM1-Pad21)") (class "Default")
      (node (ref "JM1") (pin "21") (pinfunction "21_21") (pintype "passive"))
    )
    (net (code "145") (name "unconnected-(JM1-Pad22)") (class "Default")
      (node (ref "JM1") (pin "22") (pinfunction "22_22") (pintype "passive"))
    )
    (net (code "146") (name "unconnected-(JM1-Pad23)") (class "Default")
      (node (ref "JM1") (pin "23") (pinfunction "23_23") (pintype "passive"))
    )
    (net (code "147") (name "unconnected-(JM1-Pad24)") (class "Default")
      (node (ref "JM1") (pin "24") (pinfunction "24_24") (pintype "passive"))
    )
    (net (code "148") (name "unconnected-(JM1-Pad26)") (class "Default")
      (node (ref "JM1") (pin "26") (pinfunction "26_26") (pintype "passive"))
    )
    (net (code "149") (name "unconnected-(JM1-Pad28)") (class "Default")
      (node (ref "JM1") (pin "28") (pinfunction "28_28") (pintype "passive"))
    )
    (net (code "150") (name "unconnected-(JM1-Pad31)") (class "Default")
      (node (ref "JM1") (pin "31") (pinfunction "31_31") (pintype "passive"))
    )
    (net (code "151") (name "unconnected-(JM1-Pad32)") (class "Default")
      (node (ref "JM1") (pin "32") (pinfunction "32_32") (pintype "passive"))
    )
    (net (code "152") (name "unconnected-(JM1-Pad34)") (class "Default")
      (node (ref "JM1") (pin "34") (pinfunction "34_34") (pintype "passive"))
    )
    (net (code "153") (name "unconnected-(JM1-Pad35)") (class "Default")
      (node (ref "JM1") (pin "35") (pinfunction "35_35") (pintype "passive"))
    )
    (net (code "154") (name "unconnected-(JM1-Pad36)") (class "Default")
      (node (ref "JM1") (pin "36") (pinfunction "36_36") (pintype "passive"))
    )
    (net (code "155") (name "unconnected-(JM1-Pad37)") (class "Default")
      (node (ref "JM1") (pin "37") (pinfunction "37_37") (pintype "passive"))
    )
    (net (code "156") (name "unconnected-(JM1-Pad38)") (class "Default")
      (node (ref "JM1") (pin "38") (pinfunction "38_38") (pintype "passive"))
    )
    (net (code "157") (name "unconnected-(JM1-Pad39)") (class "Default")
      (node (ref "JM1") (pin "39") (pinfunction "39_39") (pintype "passive"))
    )
    (net (code "158") (name "unconnected-(JM1-Pad40)") (class "Default")
      (node (ref "JM1") (pin "40") (pinfunction "40_40") (pintype "passive"))
    )
    (net (code "159") (name "unconnected-(JM1-Pad41)") (class "Default")
      (node (ref "JM1") (pin "41") (pinfunction "41_41") (pintype "passive"))
    )
    (net (code "160") (name "unconnected-(JM1-Pad42)") (class "Default")
      (node (ref "JM1") (pin "42") (pinfunction "42_42") (pintype "passive"))
    )
    (net (code "161") (name "unconnected-(JM1-Pad44)") (class "Default")
      (node (ref "JM1") (pin "44") (pinfunction "44_44") (pintype "passive"))
    )
    (net (code "162") (name "unconnected-(JM1-Pad45)") (class "Default")
      (node (ref "JM1") (pin "45") (pinfunction "45_45") (pintype "passive"))
    )
    (net (code "163") (name "unconnected-(JM1-Pad46)") (class "Default")
      (node (ref "JM1") (pin "46") (pinfunction "46_46") (pintype "passive"))
    )
    (net (code "164") (name "unconnected-(JM1-Pad47)") (class "Default")
      (node (ref "JM1") (pin "47") (pinfunction "47_47") (pintype "passive"))
    )
    (net (code "165") (name "unconnected-(JM1-Pad48)") (class "Default")
      (node (ref "JM1") (pin "48") (pinfunction "48_48") (pintype "passive"))
    )
    (net (code "166") (name "unconnected-(JM1-Pad49)") (class "Default")
      (node (ref "JM1") (pin "49") (pinfunction "49_49") (pintype "passive"))
    )
    (net (code "167") (name "unconnected-(JM1-Pad50)") (class "Default")
      (node (ref "JM1") (pin "50") (pinfunction "50_50") (pintype "passive"))
    )
    (net (code "168") (name "unconnected-(JM1-Pad51)") (class "Default")
      (node (ref "JM1") (pin "51") (pinfunction "51_51") (pintype "passive"))
    )
    (net (code "169") (name "unconnected-(JM1-Pad52)") (class "Default")
      (node (ref "JM1") (pin "52") (pinfunction "52_52") (pintype "passive"))
    )
    (net (code "170") (name "unconnected-(JM1-Pad56)") (class "Default")
      (node (ref "JM1") (pin "56") (pinfunction "56_56") (pintype "passive"))
    )
    (net (code "171") (name "unconnected-(JM1-Pad58)") (class "Default")
      (node (ref "JM1") (pin "58") (pinfunction "58_58") (pintype "passive"))
    )
    (net (code "172") (name "unconnected-(JM1-Pad66)") (class "Default")
      (node (ref "JM1") (pin "66") (pinfunction "66_66") (pintype "passive"))
    )
    (net (code "173") (name "unconnected-(JM1-Pad68)") (class "Default")
      (node (ref "JM1") (pin "68") (pinfunction "68_68") (pintype "passive"))
    )
    (net (code "174") (name "unconnected-(JM1-Pad70)") (class "Default")
      (node (ref "JM1") (pin "70") (pinfunction "70_70") (pintype "passive"))
    )
    (net (code "175") (name "unconnected-(JM1-Pad72)") (class "Default")
      (node (ref "JM1") (pin "72") (pinfunction "72_72") (pintype "passive"))
    )
    (net (code "176") (name "unconnected-(JM1-Pad75)") (class "Default")
      (node (ref "JM1") (pin "75") (pinfunction "75_75") (pintype "passive"))
    )
    (net (code "177") (name "unconnected-(JM1-Pad77)") (class "Default")
      (node (ref "JM1") (pin "77") (pinfunction "77_77") (pintype "passive"))
    )
    (net (code "178") (name "unconnected-(JM1-Pad80)") (class "Default")
      (node (ref "JM1") (pin "80") (pinfunction "80_80") (pintype "passive"))
    )
    (net (code "179") (name "unconnected-(JM1-Pad82)") (class "Default")
      (node (ref "JM1") (pin "82") (pinfunction "82_82") (pintype "passive"))
    )
    (net (code "180") (name "unconnected-(JM1-Pad84)") (class "Default")
      (node (ref "JM1") (pin "84") (pinfunction "84_84") (pintype "passive"))
    )
    (net (code "181") (name "unconnected-(JM1-Pad86)") (class "Default")
      (node (ref "JM1") (pin "86") (pinfunction "86_86") (pintype "passive"))
    )
    (net (code "182") (name "unconnected-(JM1-Pad88)") (class "Default")
      (node (ref "JM1") (pin "88") (pinfunction "88_88") (pintype "passive"))
    )
    (net (code "183") (name "unconnected-(JM1-Pad91)") (class "Default")
      (node (ref "JM1") (pin "91") (pinfunction "91_91") (pintype "passive"))
    )
    (net (code "184") (name "unconnected-(JM1-Pad92)") (class "Default")
      (node (ref "JM1") (pin "92") (pinfunction "92_92") (pintype "passive"))
    )
    (net (code "185") (name "unconnected-(JM1-Pad98)") (class "Default")
      (node (ref "JM1") (pin "98") (pinfunction "98_98") (pintype "passive"))
    )
    (net (code "186") (name "unconnected-(JM1-Pad100)") (class "Default")
      (node (ref "JM1") (pin "100") (pinfunction "100_100") (pintype "passive"))
    )
    (net (code "187") (name "unconnected-(JM2-Pad6)") (class "Default")
      (node (ref "JM2") (pin "6") (pinfunction "6_6") (pintype "passive+no_connect"))
    )
    (net (code "188") (name "unconnected-(JM2-Pad9)") (class "Default")
      (node (ref "JM2") (pin "9") (pinfunction "9_9") (pintype "passive"))
    )
    (net (code "189") (name "unconnected-(JM2-Pad11)") (class "Default")
      (node (ref "JM2") (pin "11") (pinfunction "11_11") (pintype "passive"))
    )
    (net (code "190") (name "unconnected-(JM2-Pad12)") (class "Default")
      (node (ref "JM2") (pin "12") (pinfunction "12_12") (pintype "passive"))
    )
    (net (code "191") (name "unconnected-(JM2-Pad13)") (class "Default")
      (node (ref "JM2") (pin "13") (pinfunction "13_13") (pintype "passive"))
    )
    (net (code "192") (name "unconnected-(JM2-Pad14)") (class "Default")
      (node (ref "JM2") (pin "14") (pinfunction "14_14") (pintype "passive"))
    )
    (net (code "193") (name "unconnected-(JM2-Pad15)") (class "Default")
      (node (ref "JM2") (pin "15") (pinfunction "15_15") (pintype "passive"))
    )
    (net (code "194") (name "unconnected-(JM2-Pad16)") (class "Default")
      (node (ref "JM2") (pin "16") (pinfunction "16_16") (pintype "passive"))
    )
    (net (code "195") (name "unconnected-(JM2-Pad18)") (class "Default")
      (node (ref "JM2") (pin "18") (pinfunction "18_18") (pintype "passive"))
    )
    (net (code "196") (name "unconnected-(JM2-Pad20)") (class "Default")
      (node (ref "JM2") (pin "20") (pinfunction "20_20") (pintype "passive"))
    )
    (net (code "197") (name "unconnected-(JM2-Pad21)") (class "Default")
      (node (ref "JM2") (pin "21") (pinfunction "21_21") (pintype "passive"))
    )
    (net (code "198") (name "unconnected-(JM2-Pad22)") (class "Default")
      (node (ref "JM2") (pin "22") (pinfunction "22_22") (pintype "passive"))
    )
    (net (code "199") (name "unconnected-(JM2-Pad23)") (class "Default")
      (node (ref "JM2") (pin "23") (pinfunction "23_23") (pintype "passive"))
    )
    (net (code "200") (name "unconnected-(JM2-Pad24)") (class "Default")
      (node (ref "JM2") (pin "24") (pinfunction "24_24") (pintype "passive"))
    )
    (net (code "201") (name "unconnected-(JM2-Pad25)") (class "Default")
      (node (ref "JM2") (pin "25") (pinfunction "25_25") (pintype "passive"))
    )
    (net (code "202") (name "unconnected-(JM2-Pad26)") (class "Default")
      (node (ref "JM2") (pin "26") (pinfunction "26_26") (pintype "passive"))
    )
    (net (code "203") (name "unconnected-(JM2-Pad27)") (class "Default")
      (node (ref "JM2") (pin "27") (pinfunction "27_27") (pintype "passive"))
    )
    (net (code "204") (name "unconnected-(JM2-Pad28)") (class "Default")
      (node (ref "JM2") (pin "28") (pinfunction "28_28") (pintype "passive"))
    )
    (net (code "205") (name "unconnected-(JM2-Pad30)") (class "Default")
      (node (ref "JM2") (pin "30") (pinfunction "30_30") (pintype "passive+no_connect"))
    )
    (net (code "206") (name "unconnected-(JM2-Pad32)") (class "Default")
      (node (ref "JM2") (pin "32") (pinfunction "32_32") (pintype "passive"))
    )
    (net (code "207") (name "unconnected-(JM2-Pad34)") (class "Default")
      (node (ref "JM2") (pin "34") (pinfunction "34_34") (pintype "passive"))
    )
    (net (code "208") (name "unconnected-(JM2-Pad36)") (class "Default")
      (node (ref "JM2") (pin "36") (pinfunction "36_36") (pintype "passive"))
    )
    (net (code "209") (name "unconnected-(JM2-Pad38)") (class "Default")
      (node (ref "JM2") (pin "38") (pinfunction "38_38") (pintype "passive"))
    )
    (net (code "210") (name "unconnected-(JM2-Pad67)") (class "Default")
      (node (ref "JM2") (pin "67") (pinfunction "67_67") (pintype "passive"))
    )
    (net (code "211") (name "unconnected-(JM2-Pad71)") (class "Default")
      (node (ref "JM2") (pin "71") (pinfunction "71_71") (pintype "passive"))
    )
    (net (code "212") (name "unconnected-(JM2-Pad72)") (class "Default")
      (node (ref "JM2") (pin "72") (pinfunction "72_72") (pintype "passive"))
    )
    (net (code "213") (name "unconnected-(JM2-Pad73)") (class "Default")
      (node (ref "JM2") (pin "73") (pinfunction "73_73") (pintype "passive"))
    )
    (net (code "214") (name "unconnected-(JM2-Pad74)") (class "Default")
      (node (ref "JM2") (pin "74") (pinfunction "74_74") (pintype "passive"))
    )
    (net (code "215") (name "unconnected-(JM2-Pad75)") (class "Default")
      (node (ref "JM2") (pin "75") (pinfunction "75_75") (pintype "passive"))
    )
    (net (code "216") (name "unconnected-(JM2-Pad76)") (class "Default")
      (node (ref "JM2") (pin "76") (pinfunction "76_76") (pintype "passive"))
    )
    (net (code "217") (name "unconnected-(JM2-Pad77)") (class "Default")
      (node (ref "JM2") (pin "77") (pinfunction "77_77") (pintype "passive"))
    )
    (net (code "218") (name "unconnected-(JM2-Pad78)") (class "Default")
      (node (ref "JM2") (pin "78") (pinfunction "78_78") (pintype "passive"))
    )
    (net (code "219") (name "unconnected-(JM2-Pad81)") (class "Default")
      (node (ref "JM2") (pin "81") (pinfunction "81_81") (pintype "passive"))
    )
    (net (code "220") (name "unconnected-(JM2-Pad82)") (class "Default")
      (node (ref "JM2") (pin "82") (pinfunction "82_82") (pintype "passive"))
    )
    (net (code "221") (name "unconnected-(JM2-Pad83)") (class "Default")
      (node (ref "JM2") (pin "83") (pinfunction "83_83") (pintype "passive"))
    )
    (net (code "222") (name "unconnected-(JM2-Pad84)") (class "Default")
      (node (ref "JM2") (pin "84") (pinfunction "84_84") (pintype "passive"))
    )
    (net (code "223") (name "unconnected-(JM2-Pad85)") (class "Default")
      (node (ref "JM2") (pin "85") (pinfunction "85_85") (pintype "passive"))
    )
    (net (code "224") (name "unconnected-(JM2-Pad86)") (class "Default")
      (node (ref "JM2") (pin "86") (pinfunction "86_86") (pintype "passive"))
    )
    (net (code "225") (name "unconnected-(JM2-Pad87)") (class "Default")
      (node (ref "JM2") (pin "87") (pinfunction "87_87") (pintype "passive"))
    )
    (net (code "226") (name "unconnected-(JM2-Pad88)") (class "Default")
      (node (ref "JM2") (pin "88") (pinfunction "88_88") (pintype "passive"))
    )
    (net (code "227") (name "unconnected-(JM2-Pad90)") (class "Default")
      (node (ref "JM2") (pin "90") (pinfunction "90_90") (pintype "passive"))
    )
    (net (code "228") (name "unconnected-(JM2-Pad91)") (class "Default")
      (node (ref "JM2") (pin "91") (pinfunction "91_91") (pintype "passive"))
    )
    (net (code "229") (name "unconnected-(JM2-Pad93)") (class "Default")
      (node (ref "JM2") (pin "93") (pinfunction "93_93") (pintype "passive"))
    )
    (net (code "230") (name "unconnected-(JM2-Pad95)") (class "Default")
      (node (ref "JM2") (pin "95") (pinfunction "95_95") (pintype "passive"))
    )
    (net (code "231") (name "unconnected-(JM2-Pad97)") (class "Default")
      (node (ref "JM2") (pin "97") (pinfunction "97_97") (pintype "passive"))
    )
    (net (code "232") (name "unconnected-(JM2-Pad99)") (class "Default")
      (node (ref "JM2") (pin "99") (pinfunction "99_99") (pintype "passive"))
    )
    (net (code "233") (name "unconnected-(JM3-Pad1)") (class "Default")
      (node (ref "JM3") (pin "1") (pinfunction "1_1") (pintype "passive"))
    )
    (net (code "234") (name "unconnected-(JM3-Pad2)") (class "Default")
      (node (ref "JM3") (pin "2") (pinfunction "2_2") (pintype "passive"))
    )
    (net (code "235") (name "unconnected-(JM3-Pad3)") (class "Default")
      (node (ref "JM3") (pin "3") (pinfunction "3_3") (pintype "passive"))
    )
    (net (code "236") (name "unconnected-(JM3-Pad4)") (class "Default")
      (node (ref "JM3") (pin "4") (pinfunction "4_4") (pintype "passive"))
    )
    (net (code "237") (name "unconnected-(JM3-Pad31)") (class "Default")
      (node (ref "JM3") (pin "31") (pinfunction "31_31") (pintype "passive"))
    )
    (net (code "238") (name "unconnected-(JM3-Pad33)") (class "Default")
      (node (ref "JM3") (pin "33") (pinfunction "33_33") (pintype "passive"))
    )
    (net (code "239") (name "unconnected-(JM3-Pad37)") (class "Default")
      (node (ref "JM3") (pin "37") (pinfunction "37_37") (pintype "passive"))
    )
    (net (code "240") (name "unconnected-(JM3-Pad38)") (class "Default")
      (node (ref "JM3") (pin "38") (pinfunction "38_38") (pintype "passive"))
    )
    (net (code "241") (name "unconnected-(JM3-Pad39)") (class "Default")
      (node (ref "JM3") (pin "39") (pinfunction "39_39") (pintype "passive"))
    )
    (net (code "242") (name "unconnected-(JM3-Pad40)") (class "Default")
      (node (ref "JM3") (pin "40") (pinfunction "40_40") (pintype "passive"))
    )
    (net (code "243") (name "unconnected-(JM3-Pad41)") (class "Default")
      (node (ref "JM3") (pin "41") (pinfunction "41_41") (pintype "passive"))
    )
    (net (code "244") (name "unconnected-(JM3-Pad42)") (class "Default")
      (node (ref "JM3") (pin "42") (pinfunction "42_42") (pintype "passive"))
    )
    (net (code "245") (name "unconnected-(JM3-Pad43)") (class "Default")
      (node (ref "JM3") (pin "43") (pinfunction "43_43") (pintype "passive"))
    )
    (net (code "246") (name "unconnected-(JM3-Pad44)") (class "Default")
      (node (ref "JM3") (pin "44") (pinfunction "44_44") (pintype "passive"))
    )
    (net (code "247") (name "unconnected-(JM3-Pad47)") (class "Default")
      (node (ref "JM3") (pin "47") (pinfunction "47_47") (pintype "passive"))
    )
    (net (code "248") (name "unconnected-(JM3-Pad48)") (class "Default")
      (node (ref "JM3") (pin "48") (pinfunction "48_48") (pintype "passive"))
    )
    (net (code "249") (name "unconnected-(JM3-Pad49)") (class "Default")
      (node (ref "JM3") (pin "49") (pinfunction "49_49") (pintype "passive"))
    )
    (net (code "250") (name "unconnected-(JM3-Pad50)") (class "Default")
      (node (ref "JM3") (pin "50") (pinfunction "50_50") (pintype "passive"))
    )
    (net (code "251") (name "unconnected-(JM3-Pad51)") (class "Default")
      (node (ref "JM3") (pin "51") (pinfunction "51_51") (pintype "passive"))
    )
    (net (code "252") (name "unconnected-(JM3-Pad52)") (class "Default")
      (node (ref "JM3") (pin "52") (pinfunction "52_52") (pintype "passive"))
    )
    (net (code "253") (name "unconnected-(JM3-Pad53)") (class "Default")
      (node (ref "JM3") (pin "53") (pinfunction "53_53") (pintype "passive"))
    )
    (net (code "254") (name "unconnected-(JM3-Pad54)") (class "Default")
      (node (ref "JM3") (pin "54") (pinfunction "54_54") (pintype "passive"))
    )
    (net (code "255") (name "unconnected-(JM3-Pad55)") (class "Default")
      (node (ref "JM3") (pin "55") (pinfunction "55_55") (pintype "passive"))
    )
    (net (code "256") (name "unconnected-(JM3-Pad56)") (class "Default")
      (node (ref "JM3") (pin "56") (pinfunction "56_56") (pintype "passive"))
    )
    (net (code "257") (name "unconnected-(JM3-Pad57)") (class "Default")
      (node (ref "JM3") (pin "57") (pinfunction "57_57") (pintype "passive"))
    )
    (net (code "258") (name "unconnected-(JM3-Pad58)") (class "Default")
      (node (ref "JM3") (pin "58") (pinfunction "58_58") (pintype "passive"))
    )
    (net (code "259") (name "unconnected-(JM3-Pad59)") (class "Default")
      (node (ref "JM3") (pin "59") (pinfunction "59_59") (pintype "passive"))
    )
    (net (code "260") (name "unconnected-(U16-NC-Pad4)") (class "Default")
      (node (ref "U16") (pin "4") (pinfunction "NC_4") (pintype "passive+no_connect"))
    )
  )
)
